# SkyDriver_-IMU_V2.net
KiCad netlist of a schematic drawn in Altium Designer
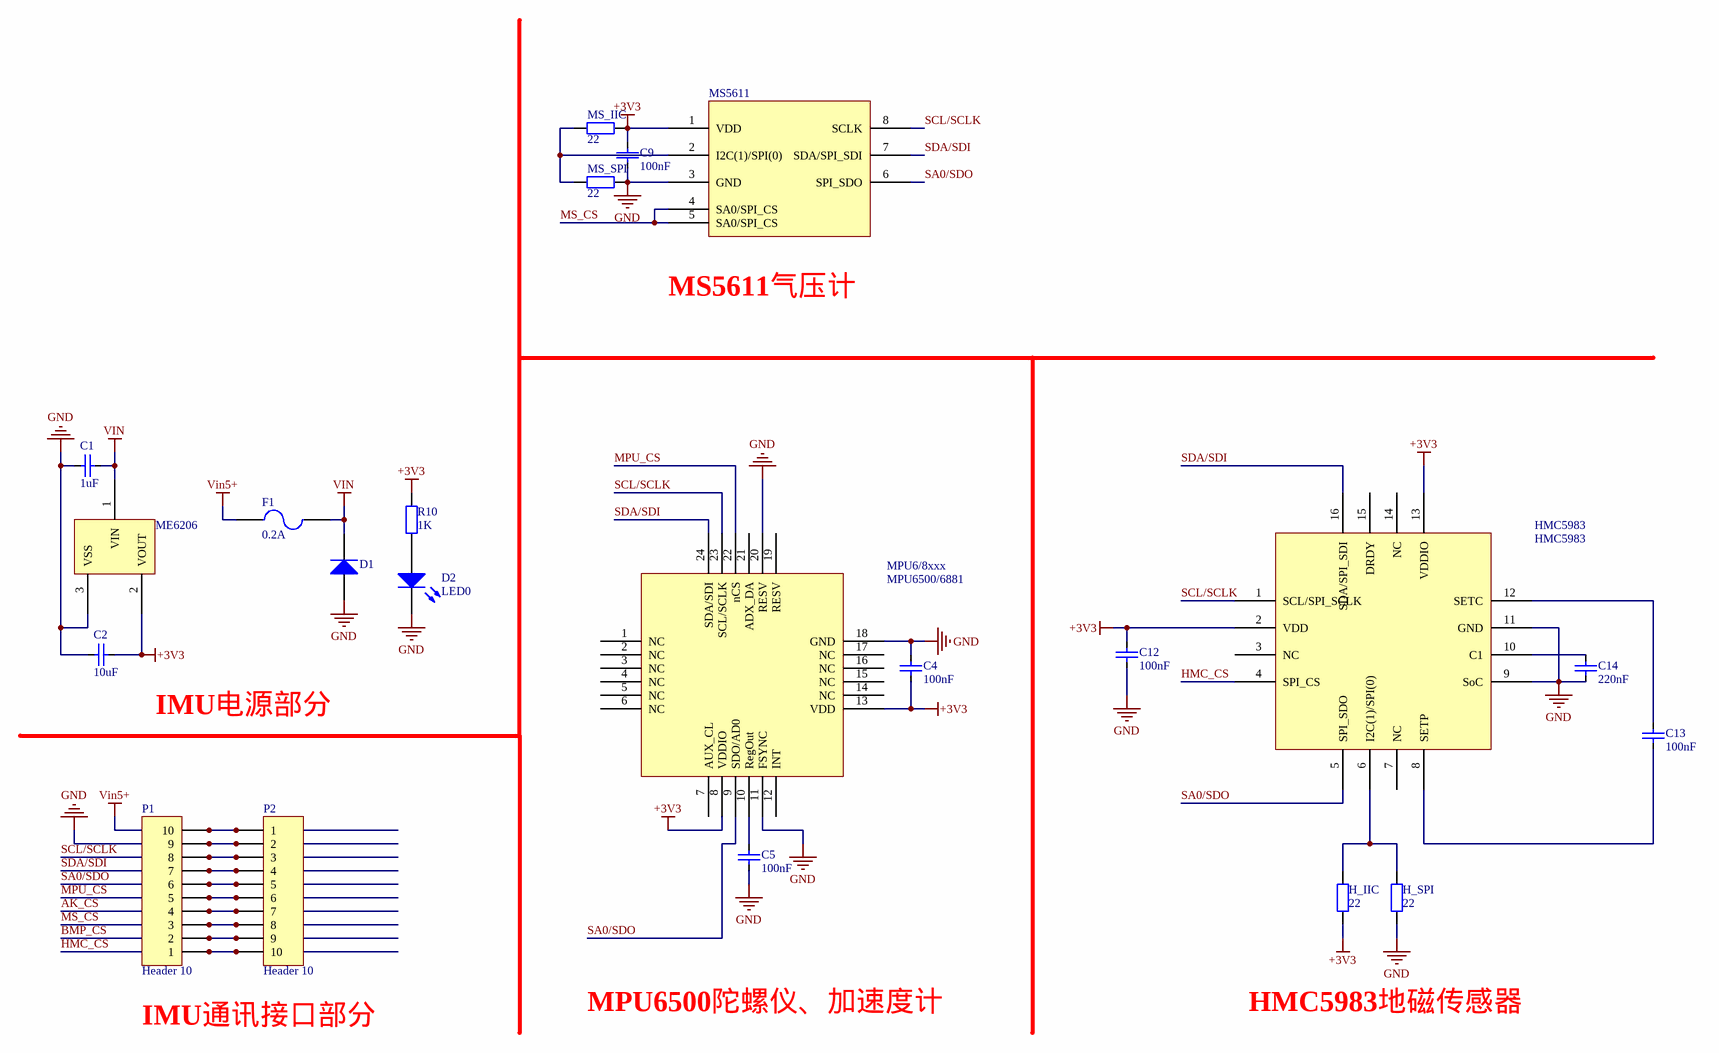
[diagram p0: SkyDriver飞行控制器-IMU板V2.SchDoc]

(export (version "E")
  (design (tool "Eeschema 10.0.6"))
  (components
    (comp (ref "C1")
      (value "1uF")
      (footprint "CAP_0603")
      (description "Capacitor")
      (fields (field (name "Comment") "Cap_0603"))
      (libsource (lib "Free Documents") (part "Cap_0603"))
    )
    (comp (ref "C2")
      (value "10uF")
      (footprint "CAP_0603")
      (description "Capacitor")
      (fields (field (name "Comment") "Cap_0603"))
      (libsource (lib "Free Documents") (part "Cap_0603"))
    )
    (comp (ref "C4")
      (value "100nF")
      (footprint "CAP_0603")
      (description "Capacitor")
      (fields (field (name "Comment") "Cap_0603"))
      (libsource (lib "Free Documents") (part "Cap_0603"))
    )
    (comp (ref "C5")
      (value "100nF")
      (footprint "CAP_0603")
      (description "Capacitor")
      (fields (field (name "Comment") "Cap_0603"))
      (libsource (lib "Free Documents") (part "Cap_0603"))
    )
    (comp (ref "C9")
      (value "100nF")
      (footprint "CAP_0603")
      (description "Capacitor")
      (fields (field (name "Comment") "Cap_0603"))
      (libsource (lib "Free Documents") (part "Cap_0603"))
    )
    (comp (ref "C12")
      (value "100nF")
      (footprint "CAP_0603")
      (description "Capacitor")
      (fields (field (name "Comment") "Cap_0603"))
      (libsource (lib "Free Documents") (part "Cap_0603"))
    )
    (comp (ref "C13")
      (value "100nF")
      (footprint "CAP_0603")
      (description "Capacitor")
      (fields (field (name "Comment") "Cap_0603"))
      (libsource (lib "Free Documents") (part "Cap_0603"))
    )
    (comp (ref "C14")
      (value "220nF")
      (footprint "CAP_0603")
      (description "Capacitor")
      (fields (field (name "Comment") "Cap_0603"))
      (libsource (lib "Free Documents") (part "Cap_0603"))
    )
    (comp (ref "D1")
      (value "SS14")
      (footprint "SOD323")
      (description "1 Amp General Purpose Rectifier")
      (fields (field (name "PUBLISHER") "Altium Limited"))
      (libsource (lib "Miscellaneous Devices") (part "Diode 1N4007"))
    )
    (comp (ref "D2")
      (value "LED0")
      (footprint "LED_0805")
      (description "Typical INFRARED GaAs LED")
      (fields (field (name "PUBLISHER") "Altium Limited"))
      (libsource (lib "STM32四轴") (part "LED0"))
    )
    (comp (ref "F1")
      (value "0.2A")
      (footprint "0805s")
      (description "保险丝")
      (fields (field (name "Comment") "Fuse") (field (name "PUBLISHER") "Altium Limited"))
      (libsource (lib "fszhang") (part "Fuse 2"))
    )
    (comp (ref "HMC5983")
      (value "HMC5983")
      (footprint "QFN16M - 3*3")
      (libsource (lib "Personal_Lib_Sch") (part "HMC5983"))
    )
    (comp (ref "H_IIC")
      (value "22")
      (footprint "RES_0603")
      (description "Resistor")
      (fields (field (name "Comment") "Res_0603"))
      (libsource (lib "Free Documents") (part "Res_0603"))
    )
    (comp (ref "H_SPI")
      (value "22")
      (footprint "RES_0603")
      (description "Resistor")
      (fields (field (name "Comment") "Res_0603"))
      (libsource (lib "Free Documents") (part "Res_0603"))
    )
    (comp (ref "ME6206")
      (value "ME6206")
      (footprint "sot23_M")
      (libsource (lib "Personal_Lib_Sch") (part "ME6206"))
    )
    (comp (ref "MPU6/8xxx")
      (value "MPU6500/6881")
      (footprint "QFN24M - 3*3")
      (libsource (lib "Personal_Lib_Sch") (part "MPU6500/6881"))
    )
    (comp (ref "MS5611")
      (value "MS5611")
      (footprint "QFN8 - MS5611")
      (libsource (lib "Personal_Lib_Sch") (part "MS5611"))
    )
    (comp (ref "MS_IIC")
      (value "22")
      (footprint "RES_0603")
      (description "Resistor")
      (fields (field (name "Comment") "Res_0603"))
      (libsource (lib "") (part "Res_0603_1"))
    )
    (comp (ref "MS_SPI")
      (value "22")
      (footprint "RES_0603")
      (description "Resistor")
      (fields (field (name "Comment") "Res_0603"))
      (libsource (lib "") (part "Res_0603_1"))
    )
    (comp (ref "P1")
      (value "Header 10")
      (footprint "FPC0.5 - Header10")
      (libsource (lib "") (part "Header 10_1"))
    )
    (comp (ref "P2")
      (value "Header 10")
      (footprint "FPC0.5 - Header10")
      (libsource (lib "myLib") (part "Header 10"))
    )
    (comp (ref "R10")
      (value "1K")
      (footprint "RES_0603")
      (description "Resistor")
      (fields (field (name "Comment") "Res_0603"))
      (libsource (lib "Free Documents") (part "Res_0603"))
    )
  )
  (nets
    (net (code "1") (name "+3V3") (class "Default")
      (node (ref "C12") (pin "2") (pinfunction "2_2") (pintype "passive"))
      (node (ref "C2") (pin "1") (pinfunction "1_1") (pintype "passive"))
      (node (ref "C4") (pin "1") (pinfunction "1_1") (pintype "passive"))
      (node (ref "C9") (pin "2") (pinfunction "2_2") (pintype "passive"))
      (node (ref "HMC5983") (pin "13") (pinfunction "VDDIO_13") (pintype "passive"))
      (node (ref "HMC5983") (pin "2") (pinfunction "VDD_2") (pintype "passive"))
      (node (ref "H_IIC") (pin "1") (pinfunction "1_1") (pintype "passive"))
      (node (ref "ME6206") (pin "2") (pinfunction "VOUT_2") (pintype "passive"))
      (node (ref "MPU6/8xxx") (pin "13") (pinfunction "VDD_13") (pintype "passive"))
      (node (ref "MPU6/8xxx") (pin "8") (pinfunction "VDDIO_8") (pintype "passive"))
      (node (ref "MS5611") (pin "1") (pinfunction "VDD_1") (pintype "passive"))
      (node (ref "MS_IIC") (pin "1") (pinfunction "1_1") (pintype "passive"))
      (node (ref "R10") (pin "2") (pinfunction "2_2") (pintype "passive"))
    )
    (net (code "2") (name "/AK_CS") (class "Default")
      (node (ref "P1") (pin "4") (pinfunction "4_4") (pintype "passive"))
      (node (ref "P2") (pin "7") (pinfunction "7_7") (pintype "passive"))
    )
    (net (code "3") (name "/BMP_CS") (class "Default")
      (node (ref "P1") (pin "2") (pinfunction "2_2") (pintype "passive"))
      (node (ref "P2") (pin "9") (pinfunction "9_9") (pintype "passive"))
    )
    (net (code "4") (name "/HMC_CS") (class "Default")
      (node (ref "HMC5983") (pin "4") (pinfunction "SPI_CS_4") (pintype "passive"))
      (node (ref "P1") (pin "1") (pinfunction "1_1") (pintype "passive"))
      (node (ref "P2") (pin "10") (pinfunction "10_10") (pintype "passive"))
    )
    (net (code "5") (name "/MPU_CS") (class "Default")
      (node (ref "MPU6/8xxx") (pin "22") (pinfunction "nCS_22") (pintype "passive"))
      (node (ref "P1") (pin "5") (pinfunction "5_5") (pintype "passive"))
      (node (ref "P2") (pin "6") (pinfunction "6_6") (pintype "passive"))
    )
    (net (code "6") (name "/MS_CS") (class "Default")
      (node (ref "MS5611") (pin "4") (pinfunction "SA0/SPI_CS_4") (pintype "passive"))
      (node (ref "MS5611") (pin "5") (pinfunction "SA0/SPI_CS_5") (pintype "passive"))
      (node (ref "P1") (pin "3") (pinfunction "3_3") (pintype "passive"))
      (node (ref "P2") (pin "8") (pinfunction "8_8") (pintype "passive"))
    )
    (net (code "7") (name "/SA0{slash}SDO") (class "Default")
      (node (ref "HMC5983") (pin "5") (pinfunction "SPI_SDO_5") (pintype "passive"))
      (node (ref "MPU6/8xxx") (pin "9") (pinfunction "SDO/AD0_9") (pintype "passive"))
      (node (ref "MS5611") (pin "6") (pinfunction "SPI_SDO_6") (pintype "passive"))
      (node (ref "P1") (pin "6") (pinfunction "6_6") (pintype "passive"))
      (node (ref "P2") (pin "5") (pinfunction "5_5") (pintype "passive"))
    )
    (net (code "8") (name "/SCL{slash}SCLK") (class "Default")
      (node (ref "HMC5983") (pin "1") (pinfunction "SCL/SPI_SCLK_1") (pintype "passive"))
      (node (ref "MPU6/8xxx") (pin "23") (pinfunction "SCL/SCLK_23") (pintype "passive"))
      (node (ref "MS5611") (pin "8") (pinfunction "SCLK_8") (pintype "passive"))
      (node (ref "P1") (pin "8") (pinfunction "8_8") (pintype "passive"))
      (node (ref "P2") (pin "3") (pinfunction "3_3") (pintype "passive"))
    )
    (net (code "9") (name "/SDA{slash}SDI") (class "Default")
      (node (ref "HMC5983") (pin "16") (pinfunction "SDA/SPI_SDI_16") (pintype "passive"))
      (node (ref "MPU6/8xxx") (pin "24") (pinfunction "SDA/SDI_24") (pintype "passive"))
      (node (ref "MS5611") (pin "7") (pinfunction "SDA/SPI_SDI_7") (pintype "passive"))
      (node (ref "P1") (pin "7") (pinfunction "7_7") (pintype "passive"))
      (node (ref "P2") (pin "4") (pinfunction "4_4") (pintype "passive"))
    )
    (net (code "10") (name "GND") (class "Default")
      (node (ref "C1") (pin "2") (pinfunction "2_2") (pintype "passive"))
      (node (ref "C12") (pin "1") (pinfunction "1_1") (pintype "passive"))
      (node (ref "C14") (pin "1") (pinfunction "1_1") (pintype "passive"))
      (node (ref "C2") (pin "2") (pinfunction "2_2") (pintype "passive"))
      (node (ref "C4") (pin "2") (pinfunction "2_2") (pintype "passive"))
      (node (ref "C5") (pin "1") (pinfunction "1_1") (pintype "passive"))
      (node (ref "C9") (pin "1") (pinfunction "1_1") (pintype "passive"))
      (node (ref "D1") (pin "2") (pinfunction "A_2") (pintype "passive"))
      (node (ref "D2") (pin "2") (pinfunction "K_2") (pintype "passive"))
      (node (ref "HMC5983") (pin "11") (pinfunction "GND_11") (pintype "passive"))
      (node (ref "HMC5983") (pin "9") (pinfunction "SoC_9") (pintype "passive"))
      (node (ref "H_SPI") (pin "1") (pinfunction "1_1") (pintype "passive"))
      (node (ref "ME6206") (pin "3") (pinfunction "VSS_3") (pintype "passive"))
      (node (ref "MPU6/8xxx") (pin "11") (pinfunction "FSYNC_11") (pintype "passive"))
      (node (ref "MPU6/8xxx") (pin "18") (pinfunction "GND_18") (pintype "passive"))
      (node (ref "MPU6/8xxx") (pin "20") (pinfunction "RESV_20") (pintype "passive"))
      (node (ref "MS5611") (pin "3") (pinfunction "GND_3") (pintype "passive"))
      (node (ref "MS_SPI") (pin "1") (pinfunction "1_1") (pintype "passive"))
      (node (ref "P1") (pin "9") (pinfunction "9_9") (pintype "passive"))
      (node (ref "P2") (pin "2") (pinfunction "2_2") (pintype "passive"))
    )
    (net (code "11") (name "Net-(D2-A)") (class "Default")
      (node (ref "D2") (pin "1") (pinfunction "A_1") (pintype "passive"))
      (node (ref "R10") (pin "1") (pinfunction "1_1") (pintype "passive"))
    )
    (net (code "12") (name "Net-(HMC5983-C1)") (class "Default")
      (node (ref "C14") (pin "2") (pinfunction "2_2") (pintype "passive"))
      (node (ref "HMC5983") (pin "10") (pinfunction "C1_10") (pintype "passive"))
    )
    (net (code "13") (name "Net-(HMC5983-I2C(1){slash}SPI(0))") (class "Default")
      (node (ref "HMC5983") (pin "6") (pinfunction "I2C(1)/SPI(0)_6") (pintype "passive"))
      (node (ref "H_IIC") (pin "2") (pinfunction "2_2") (pintype "passive"))
      (node (ref "H_SPI") (pin "2") (pinfunction "2_2") (pintype "passive"))
    )
    (net (code "14") (name "Net-(HMC5983-SETC)") (class "Default")
      (node (ref "C13") (pin "2") (pinfunction "2_2") (pintype "passive"))
      (node (ref "HMC5983") (pin "12") (pinfunction "SETC_12") (pintype "passive"))
    )
    (net (code "15") (name "Net-(HMC5983-SETP)") (class "Default")
      (node (ref "C13") (pin "1") (pinfunction "1_1") (pintype "passive"))
      (node (ref "HMC5983") (pin "8") (pinfunction "SETP_8") (pintype "passive"))
    )
    (net (code "16") (name "Net-(MPU6/8xxx-RegOut)") (class "Default")
      (node (ref "C5") (pin "2") (pinfunction "2_2") (pintype "passive"))
      (node (ref "MPU6/8xxx") (pin "10") (pinfunction "RegOut_10") (pintype "passive"))
    )
    (net (code "17") (name "Net-(MS5611-I2C(1){slash}SPI(0))") (class "Default")
      (node (ref "MS5611") (pin "2") (pinfunction "I2C(1)/SPI(0)_2") (pintype "passive"))
      (node (ref "MS_IIC") (pin "2") (pinfunction "2_2") (pintype "passive"))
      (node (ref "MS_SPI") (pin "2") (pinfunction "2_2") (pintype "passive"))
    )
    (net (code "18") (name "VIN") (class "Default")
      (node (ref "C1") (pin "1") (pinfunction "1_1") (pintype "passive"))
      (node (ref "D1") (pin "1") (pinfunction "K_1") (pintype "passive"))
      (node (ref "F1") (pin "2") (pinfunction "2_2") (pintype "passive"))
      (node (ref "ME6206") (pin "1") (pinfunction "VIN_1") (pintype "passive"))
    )
    (net (code "19") (name "Vin5+") (class "Default")
      (node (ref "F1") (pin "1") (pinfunction "1_1") (pintype "passive"))
      (node (ref "P1") (pin "10") (pinfunction "10_10") (pintype "passive"))
      (node (ref "P2") (pin "1") (pinfunction "1_1") (pintype "passive"))
    )
    (net (code "20") (name "unconnected-(HMC5983-DRDY-Pad15)") (class "Default")
      (node (ref "HMC5983") (pin "15") (pinfunction "DRDY_15") (pintype "passive"))
    )
    (net (code "21") (name "unconnected-(HMC5983-NC-Pad3)") (class "Default")
      (node (ref "HMC5983") (pin "3") (pinfunction "NC_3") (pintype "passive"))
    )
    (net (code "22") (name "unconnected-(HMC5983-NC-Pad7)") (class "Default")
      (node (ref "HMC5983") (pin "7") (pinfunction "NC_7") (pintype "passive"))
    )
    (net (code "23") (name "unconnected-(HMC5983-NC-Pad14)") (class "Default")
      (node (ref "HMC5983") (pin "14") (pinfunction "NC_14") (pintype "passive"))
    )
    (net (code "24") (name "unconnected-(MPU6/8xxx-ADX_DA-Pad21)") (class "Default")
      (node (ref "MPU6/8xxx") (pin "21") (pinfunction "ADX_DA_21") (pintype "passive"))
    )
    (net (code "25") (name "unconnected-(MPU6/8xxx-AUX_CL-Pad7)") (class "Default")
      (node (ref "MPU6/8xxx") (pin "7") (pinfunction "AUX_CL_7") (pintype "passive"))
    )
    (net (code "26") (name "unconnected-(MPU6/8xxx-INT-Pad12)") (class "Default")
      (node (ref "MPU6/8xxx") (pin "12") (pinfunction "INT_12") (pintype "passive"))
    )
    (net (code "27") (name "unconnected-(MPU6/8xxx-NC-Pad1)") (class "Default")
      (node (ref "MPU6/8xxx") (pin "1") (pinfunction "NC_1") (pintype "passive"))
    )
    (net (code "28") (name "unconnected-(MPU6/8xxx-NC-Pad2)") (class "Default")
      (node (ref "MPU6/8xxx") (pin "2") (pinfunction "NC_2") (pintype "passive"))
    )
    (net (code "29") (name "unconnected-(MPU6/8xxx-NC-Pad3)") (class "Default")
      (node (ref "MPU6/8xxx") (pin "3") (pinfunction "NC_3") (pintype "passive"))
    )
    (net (code "30") (name "unconnected-(MPU6/8xxx-NC-Pad4)") (class "Default")
      (node (ref "MPU6/8xxx") (pin "4") (pinfunction "NC_4") (pintype "passive"))
    )
    (net (code "31") (name "unconnected-(MPU6/8xxx-NC-Pad5)") (class "Default")
      (node (ref "MPU6/8xxx") (pin "5") (pinfunction "NC_5") (pintype "passive"))
    )
    (net (code "32") (name "unconnected-(MPU6/8xxx-NC-Pad6)") (class "Default")
      (node (ref "MPU6/8xxx") (pin "6") (pinfunction "NC_6") (pintype "passive"))
    )
    (net (code "33") (name "unconnected-(MPU6/8xxx-NC-Pad14)") (class "Default")
      (node (ref "MPU6/8xxx") (pin "14") (pinfunction "NC_14") (pintype "passive"))
    )
    (net (code "34") (name "unconnected-(MPU6/8xxx-NC-Pad15)") (class "Default")
      (node (ref "MPU6/8xxx") (pin "15") (pinfunction "NC_15") (pintype "passive"))
    )
    (net (code "35") (name "unconnected-(MPU6/8xxx-NC-Pad16)") (class "Default")
      (node (ref "MPU6/8xxx") (pin "16") (pinfunction "NC_16") (pintype "passive"))
    )
    (net (code "36") (name "unconnected-(MPU6/8xxx-NC-Pad17)") (class "Default")
      (node (ref "MPU6/8xxx") (pin "17") (pinfunction "NC_17") (pintype "passive"))
    )
    (net (code "37") (name "unconnected-(MPU6/8xxx-RESV-Pad19)") (class "Default")
      (node (ref "MPU6/8xxx") (pin "19") (pinfunction "RESV_19") (pintype "passive"))
    )
  )
)
